# Sheet1.net
KiCad netlist of a schematic drawn in Altium Designer
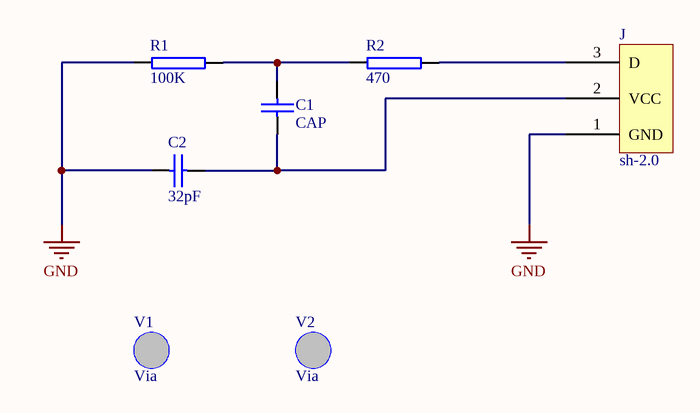
[diagram p0: Sheet1.SchDoc]

(export (version "E")
  (design (tool "Eeschema 10.0.6"))
  (components
    (comp (ref "C1") (value "CAP") (libsource (lib "gupeng_sch") (part "CAP")))
    (comp (ref "C2")
      (value "32pF")
      (footprint "Miscellaneous Devices:1608[0603]")
      (libsource (lib "gupeng_sch") (part "CAP"))
    )
    (comp (ref "J") (value "sh-2.0") (footprint "sh-2.0") (libsource (lib "zhangchong") (part "sh-2.0")))
    (comp (ref "R1")
      (value "100K")
      (footprint "Miscellaneous Devices:1608[0603]")
      (libsource (lib "gupeng_sch") (part "RES"))
    )
    (comp (ref "R2")
      (value "470")
      (footprint "Miscellaneous Devices:1608[0603]")
      (libsource (lib "gupeng_sch") (part "RES"))
    )
    (comp (ref "V1") (value "Via") (footprint "zhangchong:Via") (libsource (lib "zhangchong") (part "Via")))
    (comp (ref "V2") (value "Via") (footprint "zhangchong:Via") (libsource (lib "zhangchong") (part "Via")))
  )
  (nets
    (net (code "1") (name "GND") (class "Default")
      (node (ref "C2") (pin "1") (pinfunction "1_1") (pintype "passive"))
      (node (ref "J") (pin "1") (pinfunction "GND_1") (pintype "passive"))
      (node (ref "R1") (pin "1") (pinfunction "1_1") (pintype "passive"))
    )
    (net (code "2") (name "Net-(C1-Pad1)") (class "Default")
      (node (ref "C1") (pin "1") (pinfunction "1_1") (pintype "passive"))
      (node (ref "R1") (pin "2") (pinfunction "2_2") (pintype "passive"))
      (node (ref "R2") (pin "1") (pinfunction "1_1") (pintype "passive"))
    )
    (net (code "3") (name "Net-(J-D)") (class "Default")
      (node (ref "J") (pin "3") (pinfunction "D_3") (pintype "passive"))
      (node (ref "R2") (pin "2") (pinfunction "2_2") (pintype "passive"))
    )
    (net (code "4") (name "Net-(J-VCC)") (class "Default")
      (node (ref "C1") (pin "2") (pinfunction "2_2") (pintype "passive"))
      (node (ref "C2") (pin "2") (pinfunction "2_2") (pintype "passive"))
      (node (ref "J") (pin "2") (pinfunction "VCC_2") (pintype "passive"))
    )
  )
)
